# Adafruit_ESP8266_Feather.net
KiCad netlist of a schematic drawn in Altium Designer
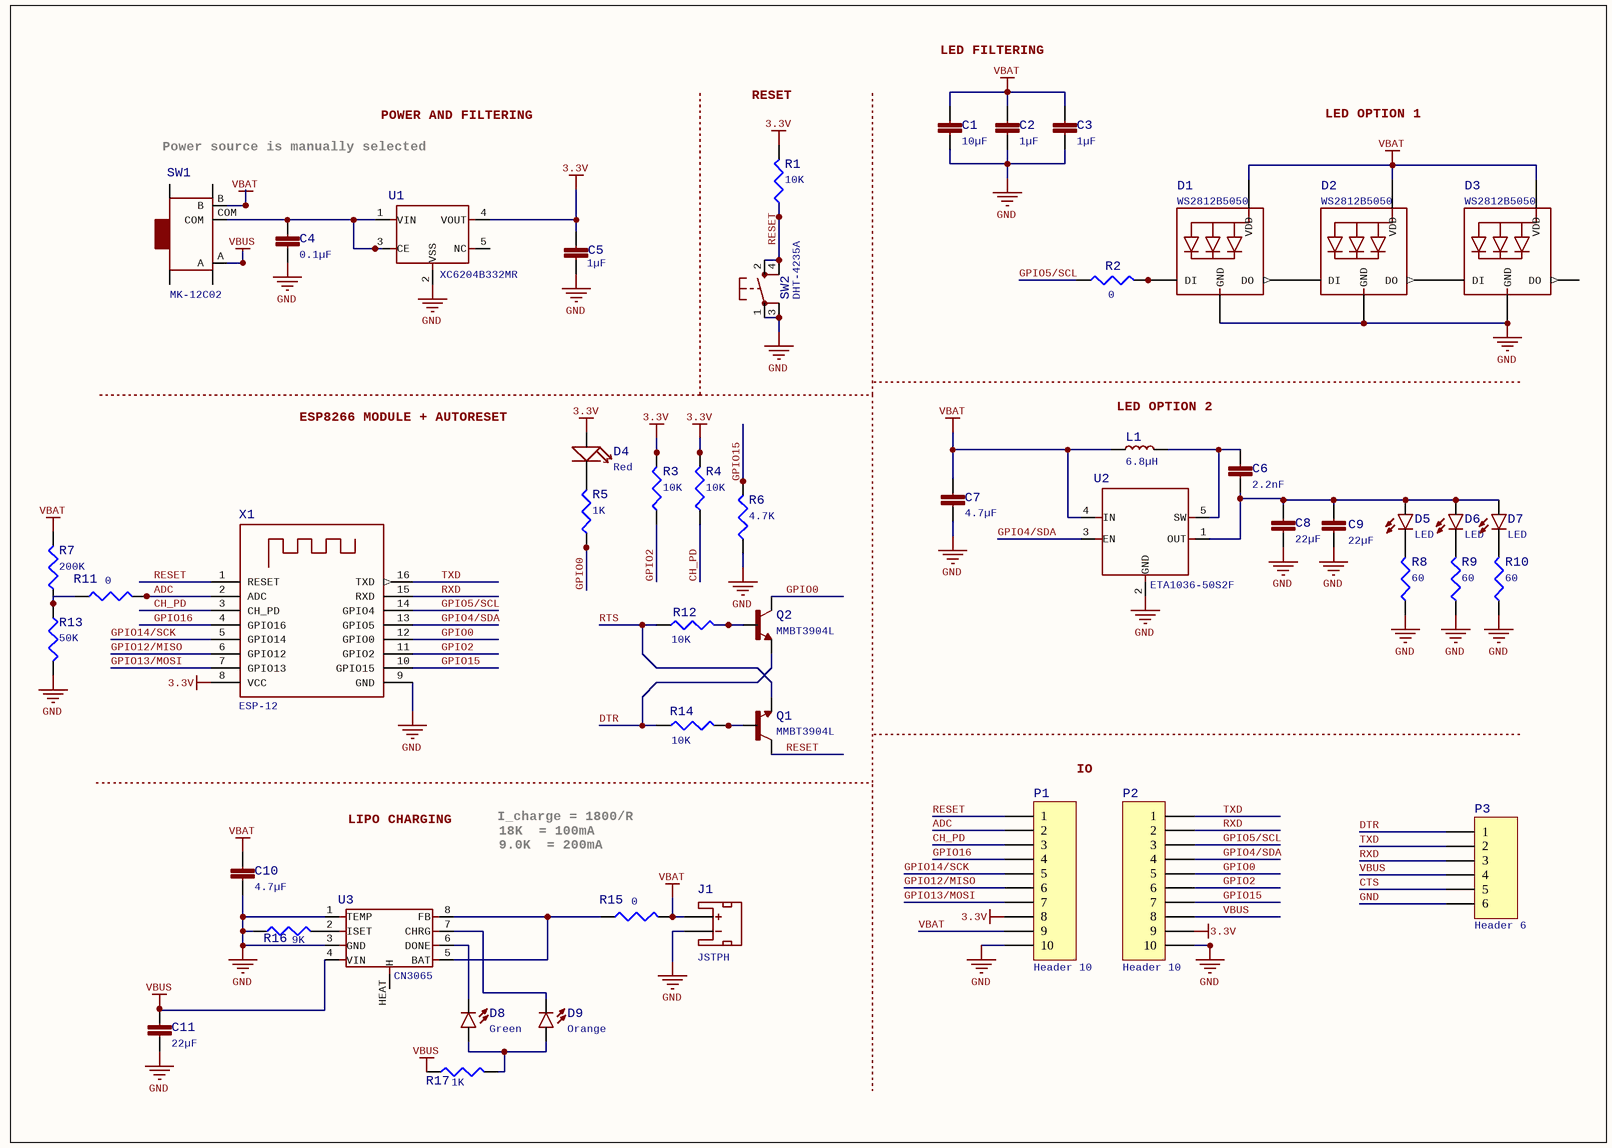
[diagram p0: Adafruit ESP8266 Feather.SchDoc]

(export (version "E")
  (design (tool "Eeschema 10.0.6"))
  (components
    (comp (ref "C1")
      (value "10µF")
      (footprint "0805")
      (libsource (lib "SparkFun-Capacitors") (part "10UF-0805-10V-10%"))
    )
    (comp (ref "C2")
      (value "1µF")
      (footprint "0603")
      (libsource (lib "SparkFun-Capacitors") (part "1.0UF-0603-16V-10%"))
    )
    (comp (ref "C3")
      (value "1µF")
      (footprint "0603")
      (libsource (lib "SparkFun-Capacitors") (part "1.0UF-0603-16V-10%"))
    )
    (comp (ref "C4")
      (value "0.1µF")
      (footprint "0805")
      (libsource (lib "SparkFun-Capacitors") (part "10UF-0805-10V-10%"))
    )
    (comp (ref "C5")
      (value "1µF")
      (footprint "0603")
      (libsource (lib "SparkFun-Capacitors") (part "1.0UF-0603-16V-10%"))
    )
    (comp (ref "C6")
      (value "2.2nF")
      (footprint "0603")
      (libsource (lib "SparkFun-Capacitors") (part "1.0UF-0603-16V-10%"))
    )
    (comp (ref "C7")
      (value "4.7µF")
      (footprint "0805")
      (libsource (lib "SparkFun-Capacitors") (part "10UF-0805-10V-10%"))
    )
    (comp (ref "C8")
      (value "22µF")
      (footprint "0805")
      (libsource (lib "SparkFun-Capacitors") (part "10UF-0805-10V-10%"))
    )
    (comp (ref "C9")
      (value "22µF")
      (footprint "0805")
      (libsource (lib "SparkFun-Capacitors") (part "10UF-0805-10V-10%"))
    )
    (comp (ref "C10")
      (value "4.7µF")
      (footprint "0805")
      (libsource (lib "SparkFun-Capacitors") (part "10UF-0805-10V-10%"))
    )
    (comp (ref "C11")
      (value "22µF")
      (footprint "0805")
      (libsource (lib "SparkFun-Capacitors") (part "10UF-0805-10V-10%"))
    )
    (comp (ref "D1")
      (value "WS2812B5050")
      (footprint "WS2812B")
      (libsource (lib "adafruit") (part "WS2812B5050"))
    )
    (comp (ref "D2")
      (value "WS2812B5050")
      (footprint "WS2812B")
      (libsource (lib "adafruit") (part "WS2812B5050"))
    )
    (comp (ref "D3")
      (value "WS2812B5050")
      (footprint "WS2812B")
      (libsource (lib "adafruit") (part "WS2812B5050"))
    )
    (comp (ref "D4") (value "Red") (footprint "LED-0603") (libsource (lib "Discrete") (part "LED-0603")))
    (comp (ref "D5") (value "LED") (footprint "LED_5MM") (libsource (lib "SparkFun-LED") (part "LED5MM")))
    (comp (ref "D6") (value "LED") (footprint "LED_5MM") (libsource (lib "SparkFun-LED") (part "LED5MM")))
    (comp (ref "D7") (value "LED") (footprint "LED_5MM") (libsource (lib "SparkFun-LED") (part "LED5MM")))
    (comp (ref "D8")
      (value "Green")
      (footprint "LED-0603")
      (libsource (lib "SparkFun-LED") (part "LED-RED0603"))
    )
    (comp (ref "D9")
      (value "Orange")
      (footprint "LED-0603")
      (libsource (lib "SparkFun-LED") (part "LED-RED0603"))
    )
    (comp (ref "J1")
      (value "JSTPH")
      (footprint "JST-2-SMD")
      (libsource (lib "SparkFun-Connectors") (part "JST_2MM_MALE"))
    )
    (comp (ref "L1")
      (value "6.8µH")
      (footprint "L0603")
      (libsource (lib "Discrete") (part "INDUCTOR/FERRITE-BEAD-0603"))
    )
    (comp (ref "P1")
      (value "Header 10")
      (footprint "HDR1X10")
      (description "Header, 10-Pin")
      (fields (field (name "PUBLISHER") "Altium Limited"))
      (libsource (lib "") (part "Header 10_1"))
    )
    (comp (ref "P2")
      (value "Header 10")
      (footprint "HDR1X10")
      (description "Header, 10-Pin")
      (fields (field (name "PUBLISHER") "Altium Limited"))
      (libsource (lib "Miscellaneous Connectors") (part "Header 10"))
    )
    (comp (ref "P3")
      (value "Header 6")
      (footprint "HDR1X6")
      (description "Header, 6-Pin")
      (fields (field (name "PUBLISHER") "Altium Limited"))
      (libsource (lib "Miscellaneous Connectors") (part "Header 6"))
    )
    (comp (ref "Q1")
      (value "MMBT3904L")
      (footprint "SOT23-3")
      (fields (field (name "DRAWN") "KTOWN"))
      (libsource (lib "") (part "TRANSISTOR_NPNSOT23-3_1"))
    )
    (comp (ref "Q2")
      (value "MMBT3904L")
      (footprint "SOT23-3")
      (fields (field (name "DRAWN") "KTOWN"))
      (libsource (lib "SparkFun") (part "TRANSISTOR_NPNSOT23-3"))
    )
    (comp (ref "R1")
      (value "10K")
      (footprint "J1-0603")
      (description "Resistor")
      (fields (field (name "Comment") "Res3") (field (name "PUBLISHER") "Altium Limited"))
      (libsource (lib "Miscellaneous Devices") (part "Res3"))
    )
    (comp (ref "R2")
      (value "0")
      (footprint "J1-0603")
      (description "Resistor")
      (fields (field (name "Comment") "Res3") (field (name "PUBLISHER") "Altium Limited"))
      (libsource (lib "Miscellaneous Devices") (part "Res3"))
    )
    (comp (ref "R3")
      (value "10K")
      (footprint "J1-0603")
      (description "Resistor")
      (fields (field (name "Comment") "Res3") (field (name "PUBLISHER") "Altium Limited"))
      (libsource (lib "Miscellaneous Devices") (part "Res3"))
    )
    (comp (ref "R4")
      (value "10K")
      (footprint "J1-0603")
      (description "Resistor")
      (fields (field (name "Comment") "Res3") (field (name "PUBLISHER") "Altium Limited"))
      (libsource (lib "Miscellaneous Devices") (part "Res3"))
    )
    (comp (ref "R5")
      (value "1K")
      (footprint "J1-0603")
      (description "Resistor")
      (fields (field (name "Comment") "Res3") (field (name "PUBLISHER") "Altium Limited"))
      (libsource (lib "Miscellaneous Devices") (part "Res3"))
    )
    (comp (ref "R6")
      (value "4.7K")
      (footprint "J1-0603")
      (description "Resistor")
      (fields (field (name "Comment") "Res3") (field (name "PUBLISHER") "Altium Limited"))
      (libsource (lib "Miscellaneous Devices") (part "Res3"))
    )
    (comp (ref "R7")
      (value "200K")
      (footprint "J1-0603")
      (description "Resistor")
      (fields (field (name "Comment") "Res3") (field (name "PUBLISHER") "Altium Limited"))
      (libsource (lib "Miscellaneous Devices") (part "Res3"))
    )
    (comp (ref "R8")
      (value "60")
      (footprint "J1-0603")
      (description "Resistor")
      (fields (field (name "Comment") "Res3") (field (name "PUBLISHER") "Altium Limited"))
      (libsource (lib "Miscellaneous Devices") (part "Res3"))
    )
    (comp (ref "R9")
      (value "60")
      (footprint "J1-0603")
      (description "Resistor")
      (fields (field (name "Comment") "Res3") (field (name "PUBLISHER") "Altium Limited"))
      (libsource (lib "Miscellaneous Devices") (part "Res3"))
    )
    (comp (ref "R10")
      (value "60")
      (footprint "J1-0603")
      (description "Resistor")
      (fields (field (name "Comment") "Res3") (field (name "PUBLISHER") "Altium Limited"))
      (libsource (lib "Miscellaneous Devices") (part "Res3"))
    )
    (comp (ref "R11")
      (value "0")
      (footprint "J1-0603")
      (description "Resistor")
      (fields (field (name "Comment") "Res3") (field (name "PUBLISHER") "Altium Limited"))
      (libsource (lib "Miscellaneous Devices") (part "Res3"))
    )
    (comp (ref "R12")
      (value "10K")
      (footprint "J1-0603")
      (description "Resistor")
      (fields (field (name "Comment") "Res3") (field (name "PUBLISHER") "Altium Limited"))
      (libsource (lib "Miscellaneous Devices") (part "Res3"))
    )
    (comp (ref "R13")
      (value "50K")
      (footprint "J1-0603")
      (description "Resistor")
      (fields (field (name "Comment") "Res3") (field (name "PUBLISHER") "Altium Limited"))
      (libsource (lib "Miscellaneous Devices") (part "Res3"))
    )
    (comp (ref "R14")
      (value "10K")
      (footprint "J1-0603")
      (description "Resistor")
      (fields (field (name "Comment") "Res3") (field (name "PUBLISHER") "Altium Limited"))
      (libsource (lib "Miscellaneous Devices") (part "Res3"))
    )
    (comp (ref "R15")
      (value "0")
      (footprint "J1-0603")
      (description "Resistor")
      (fields (field (name "Comment") "Res3") (field (name "PUBLISHER") "Altium Limited"))
      (libsource (lib "Miscellaneous Devices") (part "Res3"))
    )
    (comp (ref "R16")
      (value "9K")
      (footprint "J1-0603")
      (description "Resistor")
      (fields (field (name "Comment") "Res3") (field (name "PUBLISHER") "Altium Limited"))
      (libsource (lib "Miscellaneous Devices") (part "Res3"))
    )
    (comp (ref "R17")
      (value "1K")
      (footprint "J1-0603")
      (description "Resistor")
      (fields (field (name "Comment") "Res3") (field (name "PUBLISHER") "Altium Limited"))
      (libsource (lib "Miscellaneous Devices") (part "Res3"))
    )
    (comp (ref "SW1")
      (value "MK-12C02")
      (footprint "SW7-SMD-L6.7X2.7X3.2MM")
      (libsource (lib "Seeed-OPL-Button") (part "SMD-TOGGLE-SWITCH-ON-ON(3+4P-6.7X2.7MM)"))
    )
    (comp (ref "SW2")
      (value "DHT-4235A")
      (footprint "KMR2")
      (libsource (lib "adafruit") (part "SPST_TACT-KMR2"))
    )
    (comp (ref "U1")
      (value "XC6204B332MR")
      (footprint "SOT-23-5")
      (libsource (lib "Seeed-OPL-ic") (part "PMIC-LDO-XC6204B332MR(SOT23-5)"))
    )
    (comp (ref "U2")
      (value "ETA1036-50S2F")
      (footprint "SOT-23-5")
      (fields (field (name "MPN") "ETA1036-50S2F-T"))
      (libsource (lib "Seeed-OPL-ic") (part "PMIC-ETA1036-50S2F-T(SOT23-5)"))
    )
    (comp (ref "U3")
      (value "CN3065")
      (footprint "DFN8G-0.5-3X3MM")
      (libsource (lib "Seeed-OPL-ic") (part "PMIC-CN3065(DFN8)"))
    )
    (comp (ref "X1") (value "ESP-12") (footprint "ESP-12") (libsource (lib "adafruit") (part "ESP-12")))
  )
  (nets
    (net (code "1") (name "/ADC") (class "Default")
      (node (ref "P1") (pin "2") (pinfunction "2_2") (pintype "passive"))
      (node (ref "R11") (pin "2") (pinfunction "2_2") (pintype "passive"))
      (node (ref "X1") (pin "2") (pinfunction "ADC_2") (pintype "passive"))
    )
    (net (code "2") (name "/CH_PD") (class "Default")
      (node (ref "P1") (pin "3") (pinfunction "3_3") (pintype "passive"))
      (node (ref "R4") (pin "1") (pinfunction "1_1") (pintype "passive"))
      (node (ref "X1") (pin "3") (pinfunction "CH_PD_3") (pintype "passive"))
    )
    (net (code "3") (name "/CTS") (class "Default")
      (node (ref "P3") (pin "5") (pinfunction "5_5") (pintype "passive"))
    )
    (net (code "4") (name "/DTR") (class "Default")
      (node (ref "P3") (pin "1") (pinfunction "1_1") (pintype "passive"))
      (node (ref "Q2") (pin "2") (pinfunction "E_2") (pintype "passive"))
      (node (ref "R14") (pin "1") (pinfunction "1_1") (pintype "passive"))
    )
    (net (code "5") (name "/GPIO0") (class "Default")
      (node (ref "P2") (pin "5") (pinfunction "5_5") (pintype "passive"))
      (node (ref "Q2") (pin "3") (pinfunction "C_3") (pintype "passive"))
      (node (ref "R5") (pin "1") (pinfunction "1_1") (pintype "passive"))
      (node (ref "X1") (pin "12") (pinfunction "GPIO0_12") (pintype "passive"))
    )
    (net (code "6") (name "/GPIO2") (class "Default")
      (node (ref "P2") (pin "6") (pinfunction "6_6") (pintype "passive"))
      (node (ref "R3") (pin "1") (pinfunction "1_1") (pintype "passive"))
      (node (ref "X1") (pin "11") (pinfunction "GPIO2_11") (pintype "passive"))
    )
    (net (code "7") (name "/GPIO4{slash}SDA") (class "Default")
      (node (ref "P2") (pin "4") (pinfunction "4_4") (pintype "passive"))
      (node (ref "U2") (pin "3") (pinfunction "EN_3") (pintype "passive"))
      (node (ref "X1") (pin "13") (pinfunction "GPIO5_13") (pintype "passive"))
    )
    (net (code "8") (name "/GPIO5{slash}SCL") (class "Default")
      (node (ref "P2") (pin "3") (pinfunction "3_3") (pintype "passive"))
      (node (ref "R2") (pin "1") (pinfunction "1_1") (pintype "passive"))
      (node (ref "X1") (pin "14") (pinfunction "GPIO4_14") (pintype "passive"))
    )
    (net (code "9") (name "/GPIO12{slash}MISO") (class "Default")
      (node (ref "P1") (pin "6") (pinfunction "6_6") (pintype "passive"))
      (node (ref "X1") (pin "6") (pinfunction "GPIO12_6") (pintype "passive"))
    )
    (net (code "10") (name "/GPIO13{slash}MOSI") (class "Default")
      (node (ref "P1") (pin "7") (pinfunction "7_7") (pintype "passive"))
      (node (ref "X1") (pin "7") (pinfunction "GPIO13_7") (pintype "passive"))
    )
    (net (code "11") (name "/GPIO14{slash}SCK") (class "Default")
      (node (ref "P1") (pin "5") (pinfunction "5_5") (pintype "passive"))
      (node (ref "X1") (pin "5") (pinfunction "GPIO14_5") (pintype "passive"))
    )
    (net (code "12") (name "/GPIO15") (class "Default")
      (node (ref "P2") (pin "7") (pinfunction "7_7") (pintype "passive"))
      (node (ref "R6") (pin "2") (pinfunction "2_2") (pintype "passive"))
      (node (ref "X1") (pin "10") (pinfunction "GPIO15_10") (pintype "passive"))
    )
    (net (code "13") (name "/GPIO16") (class "Default")
      (node (ref "P1") (pin "4") (pinfunction "4_4") (pintype "passive"))
      (node (ref "X1") (pin "4") (pinfunction "GPIO16_4") (pintype "passive"))
    )
    (net (code "14") (name "/RESET") (class "Default")
      (node (ref "P1") (pin "1") (pinfunction "1_1") (pintype "passive"))
      (node (ref "Q1") (pin "3") (pinfunction "C_3") (pintype "passive"))
      (node (ref "R1") (pin "1") (pinfunction "1_1") (pintype "passive"))
      (node (ref "SW2") (pin "2") (pinfunction "S_2") (pintype "passive"))
      (node (ref "SW2") (pin "4") (pinfunction "S1_4") (pintype "passive"))
      (node (ref "X1") (pin "1") (pinfunction "RESET_1") (pintype "passive"))
    )
    (net (code "15") (name "/RTS") (class "Default")
      (node (ref "Q1") (pin "2") (pinfunction "E_2") (pintype "passive"))
      (node (ref "R12") (pin "1") (pinfunction "1_1") (pintype "passive"))
    )
    (net (code "16") (name "/RXD") (class "Default")
      (node (ref "P2") (pin "2") (pinfunction "2_2") (pintype "passive"))
      (node (ref "P3") (pin "3") (pinfunction "3_3") (pintype "passive"))
      (node (ref "X1") (pin "15") (pinfunction "RXD_15") (pintype "passive"))
    )
    (net (code "17") (name "/TXD") (class "Default")
      (node (ref "P2") (pin "1") (pinfunction "1_1") (pintype "passive"))
      (node (ref "P3") (pin "2") (pinfunction "2_2") (pintype "passive"))
      (node (ref "X1") (pin "16") (pinfunction "TXD_16") (pintype "output"))
    )
    (net (code "18") (name "3.3V") (class "Default")
      (node (ref "C5") (pin "1") (pinfunction "1_1") (pintype "passive"))
      (node (ref "D4") (pin "+") (pinfunction "+_+") (pintype "passive"))
      (node (ref "P1") (pin "8") (pinfunction "8_8") (pintype "passive"))
      (node (ref "P2") (pin "9") (pinfunction "9_9") (pintype "passive"))
      (node (ref "R1") (pin "2") (pinfunction "2_2") (pintype "passive"))
      (node (ref "R3") (pin "2") (pinfunction "2_2") (pintype "passive"))
      (node (ref "R4") (pin "2") (pinfunction "2_2") (pintype "passive"))
      (node (ref "U1") (pin "4") (pinfunction "VOUT_4") (pintype "power_in"))
      (node (ref "X1") (pin "8") (pinfunction "VCC_8") (pintype "power_in"))
    )
    (net (code "19") (name "GND") (class "Default")
      (node (ref "C1") (pin "2") (pinfunction "2_2") (pintype "passive"))
      (node (ref "C10") (pin "2") (pinfunction "2_2") (pintype "passive"))
      (node (ref "C11") (pin "2") (pinfunction "2_2") (pintype "passive"))
      (node (ref "C2") (pin "2") (pinfunction "2_2") (pintype "passive"))
      (node (ref "C3") (pin "2") (pinfunction "2_2") (pintype "passive"))
      (node (ref "C4") (pin "2") (pinfunction "2_2") (pintype "passive"))
      (node (ref "C5") (pin "2") (pinfunction "2_2") (pintype "passive"))
      (node (ref "C7") (pin "2") (pinfunction "2_2") (pintype "passive"))
      (node (ref "C8") (pin "2") (pinfunction "2_2") (pintype "passive"))
      (node (ref "C9") (pin "2") (pinfunction "2_2") (pintype "passive"))
      (node (ref "D1") (pin "3-GND") (pinfunction "GND_3-GND") (pintype "power_in"))
      (node (ref "D2") (pin "3-GND") (pinfunction "GND_3-GND") (pintype "power_in"))
      (node (ref "D3") (pin "3-GND") (pinfunction "GND_3-GND") (pintype "power_in"))
      (node (ref "J1") (pin "1") (pinfunction "-_1") (pintype "passive"))
      (node (ref "P1") (pin "10") (pinfunction "10_10") (pintype "passive"))
      (node (ref "P2") (pin "10") (pinfunction "10_10") (pintype "passive"))
      (node (ref "P3") (pin "6") (pinfunction "6_6") (pintype "passive"))
      (node (ref "R10") (pin "1") (pinfunction "1_1") (pintype "passive"))
      (node (ref "R13") (pin "2") (pinfunction "2_2") (pintype "passive"))
      (node (ref "R16") (pin "1") (pinfunction "1_1") (pintype "passive"))
      (node (ref "R6") (pin "1") (pinfunction "1_1") (pintype "passive"))
      (node (ref "R8") (pin "1") (pinfunction "1_1") (pintype "passive"))
      (node (ref "R9") (pin "1") (pinfunction "1_1") (pintype "passive"))
      (node (ref "SW2") (pin "1") (pinfunction "P_1") (pintype "passive"))
      (node (ref "SW2") (pin "3") (pinfunction "P1_3") (pintype "passive"))
      (node (ref "U1") (pin "2") (pinfunction "VSS_2") (pintype "power_in"))
      (node (ref "U2") (pin "2") (pinfunction "GND_2") (pintype "passive"))
      (node (ref "U3") (pin "1") (pinfunction "TEMP_1") (pintype "passive"))
      (node (ref "U3") (pin "3") (pinfunction "GND_3") (pintype "power_in"))
      (node (ref "X1") (pin "9") (pinfunction "GND_9") (pintype "power_in"))
    )
    (net (code "20") (name "Net-(D1-DI)") (class "Default")
      (node (ref "D1") (pin "4-DIN") (pinfunction "DI_4-DIN") (pintype "passive"))
      (node (ref "R2") (pin "2") (pinfunction "2_2") (pintype "passive"))
    )
    (net (code "21") (name "Net-(D1-DO)") (class "Default")
      (node (ref "D1") (pin "2-DOUT") (pinfunction "DO_2-DOUT") (pintype "output"))
      (node (ref "D2") (pin "4-DIN") (pinfunction "DI_4-DIN") (pintype "passive"))
    )
    (net (code "22") (name "Net-(D2-DO)") (class "Default")
      (node (ref "D2") (pin "2-DOUT") (pinfunction "DO_2-DOUT") (pintype "output"))
      (node (ref "D3") (pin "4-DIN") (pinfunction "DI_4-DIN") (pintype "passive"))
    )
    (net (code "23") (name "Net-(D4-Pad-)") (class "Default")
      (node (ref "D4") (pin "-") (pinfunction "-_-") (pintype "passive"))
      (node (ref "R5") (pin "2") (pinfunction "2_2") (pintype "passive"))
    )
    (net (code "24") (name "Net-(D5-C)") (class "Default")
      (node (ref "D5") (pin "K") (pinfunction "C_K") (pintype "passive"))
      (node (ref "R8") (pin "2") (pinfunction "2_2") (pintype "passive"))
    )
    (net (code "25") (name "Net-(D6-C)") (class "Default")
      (node (ref "D6") (pin "K") (pinfunction "C_K") (pintype "passive"))
      (node (ref "R9") (pin "2") (pinfunction "2_2") (pintype "passive"))
    )
    (net (code "26") (name "Net-(D7-C)") (class "Default")
      (node (ref "D7") (pin "K") (pinfunction "C_K") (pintype "passive"))
      (node (ref "R10") (pin "2") (pinfunction "2_2") (pintype "passive"))
    )
    (net (code "27") (name "Net-(D8-PadA)") (class "Default")
      (node (ref "D8") (pin "A") (pinfunction "A_A") (pintype "passive"))
      (node (ref "D9") (pin "A") (pinfunction "A_A") (pintype "passive"))
      (node (ref "R17") (pin "2") (pinfunction "2_2") (pintype "passive"))
    )
    (net (code "28") (name "Net-(Q1-B)") (class "Default")
      (node (ref "Q1") (pin "1") (pinfunction "B_1") (pintype "passive"))
      (node (ref "R14") (pin "2") (pinfunction "2_2") (pintype "passive"))
    )
    (net (code "29") (name "Net-(Q2-B)") (class "Default")
      (node (ref "Q2") (pin "1") (pinfunction "B_1") (pintype "passive"))
      (node (ref "R12") (pin "2") (pinfunction "2_2") (pintype "passive"))
    )
    (net (code "30") (name "Net-(R11-Pad1)") (class "Default")
      (node (ref "R11") (pin "1") (pinfunction "1_1") (pintype "passive"))
      (node (ref "R13") (pin "1") (pinfunction "1_1") (pintype "passive"))
      (node (ref "R7") (pin "1") (pinfunction "1_1") (pintype "passive"))
    )
    (net (code "31") (name "Net-(U1-CE)") (class "Default")
      (node (ref "C4") (pin "1") (pinfunction "1_1") (pintype "passive"))
      (node (ref "SW1") (pin "COM") (pinfunction "COM_COM") (pintype "passive"))
      (node (ref "U1") (pin "1") (pinfunction "VIN_1") (pintype "passive"))
      (node (ref "U1") (pin "3") (pinfunction "CE_3") (pintype "passive"))
    )
    (net (code "32") (name "Net-(U2-OUT)") (class "Default")
      (node (ref "C6") (pin "2") (pinfunction "2_2") (pintype "passive"))
      (node (ref "C8") (pin "1") (pinfunction "1_1") (pintype "passive"))
      (node (ref "C9") (pin "1") (pinfunction "1_1") (pintype "passive"))
      (node (ref "D5") (pin "A") (pinfunction "A_A") (pintype "passive"))
      (node (ref "D6") (pin "A") (pinfunction "A_A") (pintype "passive"))
      (node (ref "D7") (pin "A") (pinfunction "A_A") (pintype "passive"))
      (node (ref "U2") (pin "1") (pinfunction "OUT_1") (pintype "passive"))
    )
    (net (code "33") (name "Net-(U2-SW)") (class "Default")
      (node (ref "C6") (pin "1") (pinfunction "1_1") (pintype "passive"))
      (node (ref "L1") (pin "2") (pinfunction "2_2") (pintype "passive"))
      (node (ref "U2") (pin "5") (pinfunction "SW_5") (pintype "passive"))
    )
    (net (code "34") (name "Net-(U3-BAT)") (class "Default")
      (node (ref "R15") (pin "1") (pinfunction "1_1") (pintype "passive"))
      (node (ref "U3") (pin "5") (pinfunction "BAT_5") (pintype "passive"))
      (node (ref "U3") (pin "8") (pinfunction "FB_8") (pintype "passive"))
    )
    (net (code "35") (name "Net-(U3-CHRG)") (class "Default")
      (node (ref "D9") (pin "C") (pinfunction "C_C") (pintype "passive"))
      (node (ref "U3") (pin "7") (pinfunction "CHRG_7") (pintype "passive"))
    )
    (net (code "36") (name "Net-(U3-DONE)") (class "Default")
      (node (ref "D8") (pin "C") (pinfunction "C_C") (pintype "passive"))
      (node (ref "U3") (pin "6") (pinfunction "DONE_6") (pintype "passive"))
    )
    (net (code "37") (name "Net-(U3-ISET)") (class "Default")
      (node (ref "R16") (pin "2") (pinfunction "2_2") (pintype "passive"))
      (node (ref "U3") (pin "2") (pinfunction "ISET_2") (pintype "passive"))
    )
    (net (code "38") (name "VBAT") (class "Default")
      (node (ref "C1") (pin "1") (pinfunction "1_1") (pintype "passive"))
      (node (ref "C10") (pin "1") (pinfunction "1_1") (pintype "passive"))
      (node (ref "C2") (pin "1") (pinfunction "1_1") (pintype "passive"))
      (node (ref "C3") (pin "1") (pinfunction "1_1") (pintype "passive"))
      (node (ref "C7") (pin "1") (pinfunction "1_1") (pintype "passive"))
      (node (ref "D1") (pin "1-VDD") (pinfunction "VDD_1-VDD") (pintype "power_in"))
      (node (ref "D2") (pin "1-VDD") (pinfunction "VDD_1-VDD") (pintype "power_in"))
      (node (ref "D3") (pin "1-VDD") (pinfunction "VDD_1-VDD") (pintype "power_in"))
      (node (ref "J1") (pin "2") (pinfunction "+_2") (pintype "passive"))
      (node (ref "L1") (pin "1") (pinfunction "1_1") (pintype "passive"))
      (node (ref "P1") (pin "9") (pinfunction "9_9") (pintype "passive"))
      (node (ref "R15") (pin "2") (pinfunction "2_2") (pintype "passive"))
      (node (ref "R7") (pin "2") (pinfunction "2_2") (pintype "passive"))
      (node (ref "SW1") (pin "B") (pinfunction "B_B") (pintype "passive"))
      (node (ref "U2") (pin "4") (pinfunction "IN_4") (pintype "passive"))
    )
    (net (code "39") (name "VBUS") (class "Default")
      (node (ref "C11") (pin "1") (pinfunction "1_1") (pintype "passive"))
      (node (ref "P2") (pin "8") (pinfunction "8_8") (pintype "passive"))
      (node (ref "P3") (pin "4") (pinfunction "4_4") (pintype "passive"))
      (node (ref "R17") (pin "1") (pinfunction "1_1") (pintype "passive"))
      (node (ref "SW1") (pin "A") (pinfunction "A_A") (pintype "passive"))
      (node (ref "U3") (pin "4") (pinfunction "VIN_4") (pintype "passive"))
    )
    (net (code "40") (name "unconnected-(D3-DO-Pad2-DOUT)") (class "Default")
      (node (ref "D3") (pin "2-DOUT") (pinfunction "DO_2-DOUT") (pintype "output"))
    )
    (net (code "41") (name "unconnected-(J1-PAD1-PadNC1)") (class "Default")
      (node (ref "J1") (pin "NC1") (pinfunction "PAD1_NC1") (pintype "passive"))
    )
    (net (code "42") (name "unconnected-(J1-PAD2-PadNC2)") (class "Default")
      (node (ref "J1") (pin "NC2") (pinfunction "PAD2_NC2") (pintype "passive"))
    )
    (net (code "43") (name "unconnected-(SW1-PadSS1)") (class "Default")
      (node (ref "SW1") (pin "SS1") (pinfunction "SS1_SS1") (pintype "passive"))
    )
    (net (code "44") (name "unconnected-(SW1-PadSS2)") (class "Default")
      (node (ref "SW1") (pin "SS2") (pinfunction "SS2_SS2") (pintype "passive"))
    )
    (net (code "45") (name "unconnected-(SW1-PadSS3)") (class "Default")
      (node (ref "SW1") (pin "SS3") (pinfunction "SS3_SS3") (pintype "passive"))
    )
    (net (code "46") (name "unconnected-(SW1-PadSS4)") (class "Default")
      (node (ref "SW1") (pin "SS4") (pinfunction "SS4_SS4") (pintype "passive"))
    )
    (net (code "47") (name "unconnected-(U1-NC-Pad5)") (class "Default")
      (node (ref "U1") (pin "5") (pinfunction "NC_5") (pintype "passive"))
    )
    (net (code "48") (name "unconnected-(U3-H-PadHEAT)") (class "Default")
      (node (ref "U3") (pin "HEAT") (pinfunction "H_HEAT") (pintype "passive"))
    )
  )
)
